# Yukari_3_11DoF_2_Unrouted.net
KiCad netlist of a schematic drawn in EAGLE
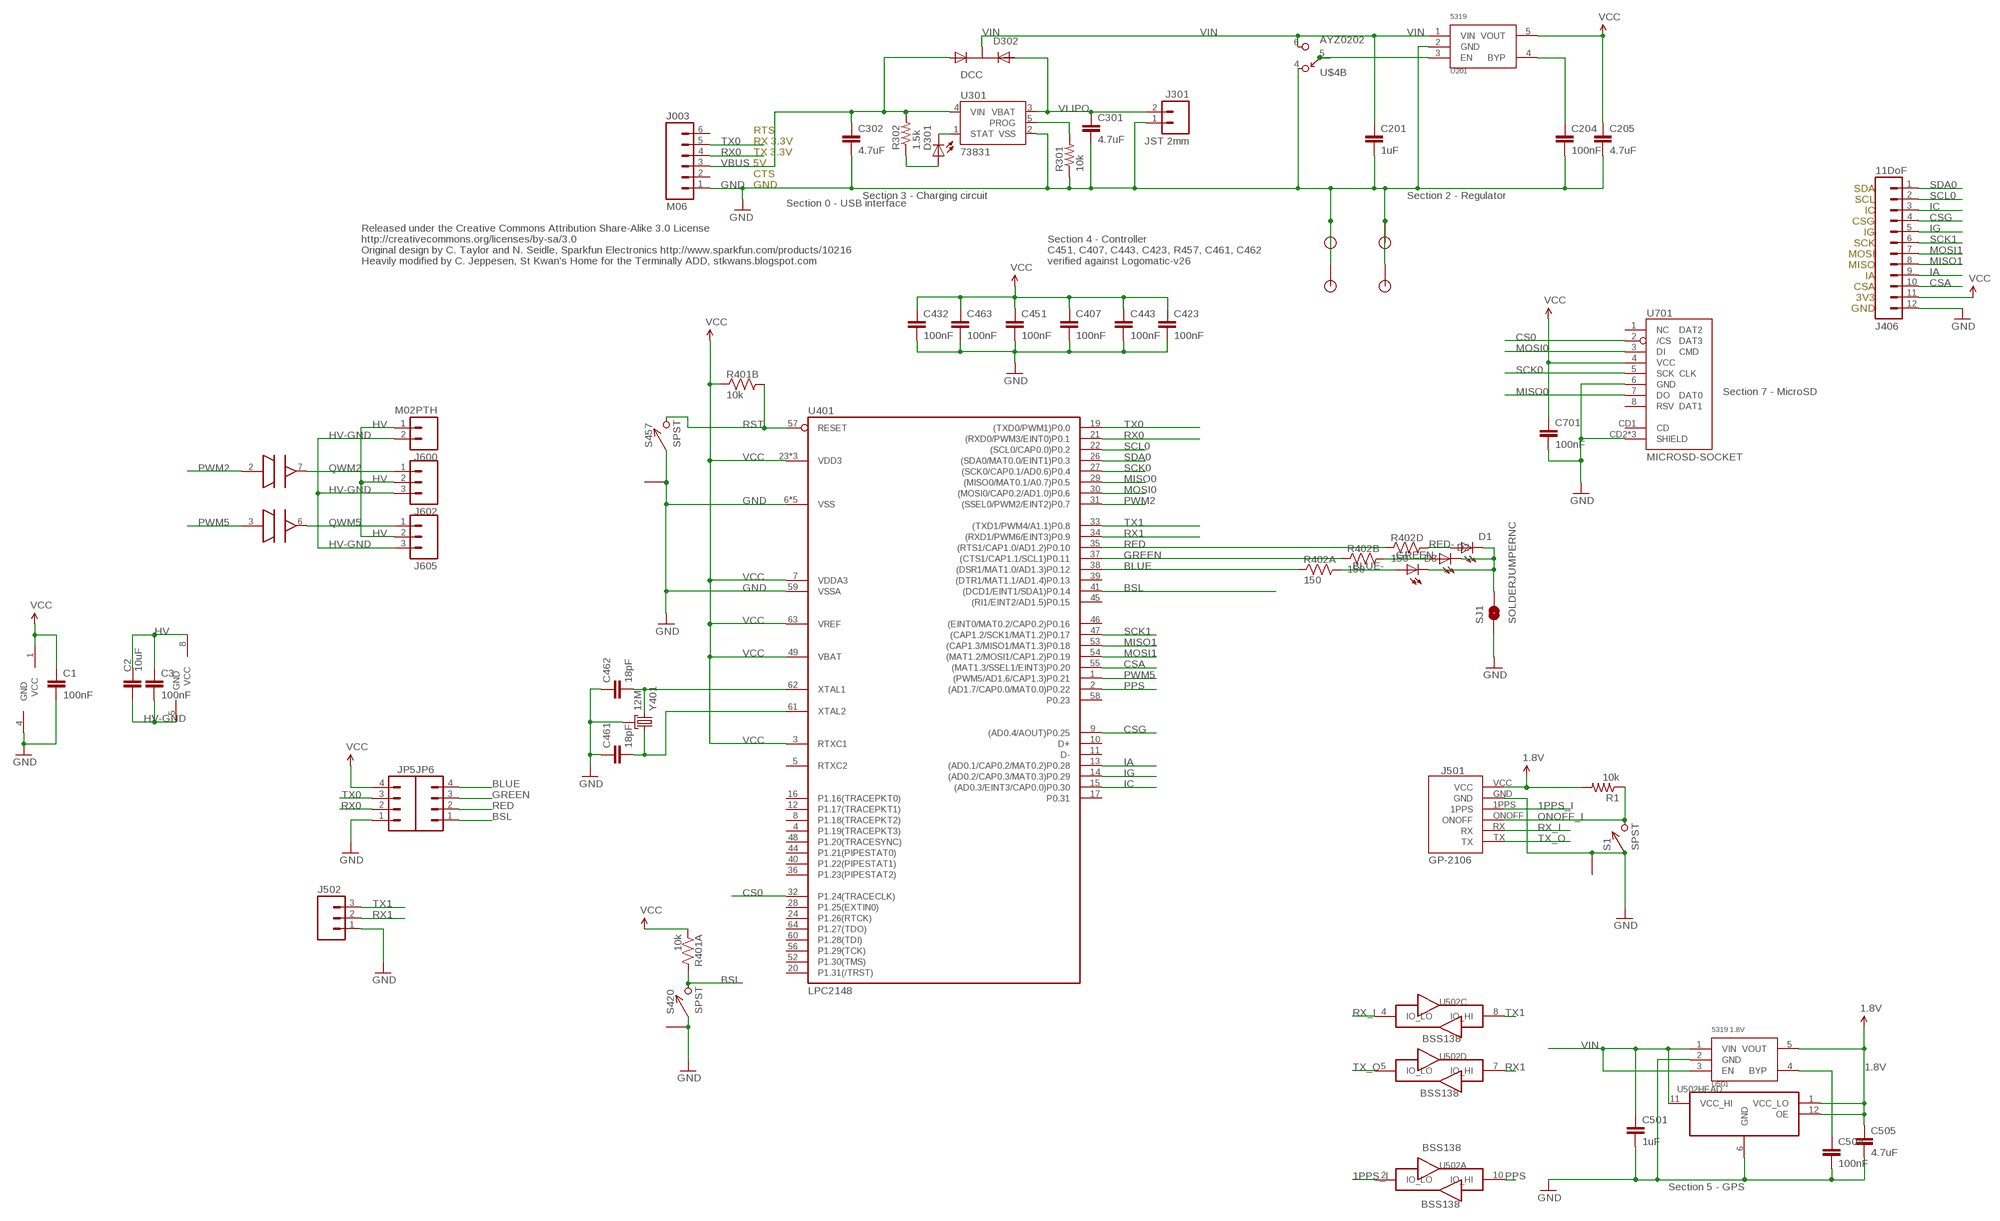
[diagram p0: schematic, sheet 1]

(export (version "E")
  (design (tool "Eeschema 10.0.6"))
  (components
    (comp (ref "C1")
      (value "100nF")
      (footprint "eagle-import:0402-CAP")
      (libsource (lib "eagle-import") (part "CAP0402-CAP"))
    )
    (comp (ref "C2")
      (value "10uF")
      (footprint "eagle-import:0603-CAP")
      (libsource (lib "eagle-import") (part "CAP0603-CAP"))
    )
    (comp (ref "C3")
      (value "100nF")
      (footprint "eagle-import:0402-CAP")
      (libsource (lib "eagle-import") (part "CAP0402-CAP"))
    )
    (comp (ref "C201")
      (value "1uF")
      (footprint "eagle-import:0402-CAP")
      (libsource (lib "eagle-import") (part "CAP0402-CAP"))
    )
    (comp (ref "C204")
      (value "100nF")
      (footprint "eagle-import:0402-CAP")
      (libsource (lib "eagle-import") (part "CAP0402-CAP"))
    )
    (comp (ref "C205")
      (value "4.7uF")
      (footprint "eagle-import:0402-CAP")
      (libsource (lib "eagle-import") (part "CAP0402-CAP"))
    )
    (comp (ref "C301")
      (value "4.7uF")
      (footprint "eagle-import:0402-CAP")
      (libsource (lib "eagle-import") (part "CAP0402-CAP"))
    )
    (comp (ref "C302")
      (value "4.7uF")
      (footprint "eagle-import:0402-CAP")
      (libsource (lib "eagle-import") (part "CAP0402-CAP"))
    )
    (comp (ref "C407")
      (value "100nF")
      (footprint "eagle-import:0402-CAP")
      (libsource (lib "eagle-import") (part "CAP0402-CAP"))
    )
    (comp (ref "C423")
      (value "100nF")
      (footprint "eagle-import:0402-CAP")
      (libsource (lib "eagle-import") (part "CAP0402-CAP"))
    )
    (comp (ref "C432")
      (value "100nF")
      (footprint "eagle-import:0402-CAP")
      (libsource (lib "eagle-import") (part "CAP0402-CAP"))
    )
    (comp (ref "C443")
      (value "100nF")
      (footprint "eagle-import:0402-CAP")
      (libsource (lib "eagle-import") (part "CAP0402-CAP"))
    )
    (comp (ref "C451")
      (value "100nF")
      (footprint "eagle-import:0402-CAP")
      (libsource (lib "eagle-import") (part "CAP0402-CAP"))
    )
    (comp (ref "C461")
      (value "18pF")
      (footprint "eagle-import:0402-CAP")
      (libsource (lib "eagle-import") (part "CAP0402-CAP"))
    )
    (comp (ref "C462")
      (value "18pF")
      (footprint "eagle-import:0402-CAP")
      (libsource (lib "eagle-import") (part "CAP0402-CAP"))
    )
    (comp (ref "C463")
      (value "100nF")
      (footprint "eagle-import:0402-CAP")
      (libsource (lib "eagle-import") (part "CAP0402-CAP"))
    )
    (comp (ref "C501")
      (value "1uF")
      (footprint "eagle-import:0402-CAP")
      (libsource (lib "eagle-import") (part "CAP0402-CAP"))
    )
    (comp (ref "C504")
      (value "100nF")
      (footprint "eagle-import:0402-CAP")
      (libsource (lib "eagle-import") (part "CAP0402-CAP"))
    )
    (comp (ref "C505")
      (value "4.7uF")
      (footprint "eagle-import:0402-CAP")
      (libsource (lib "eagle-import") (part "CAP0402-CAP"))
    )
    (comp (ref "C701")
      (value "100nF")
      (footprint "eagle-import:0402-CAP")
      (libsource (lib "eagle-import") (part "CAP0402-CAP"))
    )
    (comp (ref "D1")
      (value "RED")
      (footprint "eagle-import:LED-0603")
      (libsource (lib "eagle-import") (part "LED0603"))
    )
    (comp (ref "D2")
      (value "GREEN")
      (footprint "eagle-import:LED-0603")
      (libsource (lib "eagle-import") (part "LED0603"))
    )
    (comp (ref "D3")
      (value "BLUE")
      (footprint "eagle-import:LED-0603")
      (libsource (lib "eagle-import") (part "LED0603"))
    )
    (comp (ref "D301")
      (value "RED")
      (footprint "eagle-import:LED-0603")
      (libsource (lib "eagle-import") (part "LED0603"))
    )
    (comp (ref "D302")
      (value "DCC")
      (footprint "eagle-import:SOT-23-3")
      (libsource (lib "eagle-import") (part "PMEG2005CT"))
    )
    (comp (ref "J003")
      (value "M06")
      (footprint "eagle-import:1X06")
      (libsource (lib "eagle-import") (part "M06SIP"))
    )
    (comp (ref "J301")
      (value "JST 2mm")
      (footprint "eagle-import:JST-2-SMD")
      (libsource (lib "eagle-import") (part "M02-JST-2MM-SMT"))
    )
    (comp (ref "J406")
      (value "11DoF")
      (footprint "eagle-import:1X12")
      (libsource (lib "eagle-import") (part "M12PTH"))
    )
    (comp (ref "J501")
      (value "GP-2106")
      (footprint "eagle-import:GP-2106")
      (libsource (lib "eagle-import") (part "GP-2106"))
    )
    (comp (ref "J502")
      (value "M03PTH")
      (footprint "eagle-import:1X03")
      (libsource (lib "eagle-import") (part "M03PTH"))
    )
    (comp (ref "J600")
      (value "M02PTH")
      (footprint "eagle-import:1X02")
      (libsource (lib "eagle-import") (part "SparkFun-Connectors_M02PTH"))
    )
    (comp (ref "J602")
      (value "M03PTH")
      (footprint "eagle-import:1X03")
      (libsource (lib "eagle-import") (part "M03PTH"))
    )
    (comp (ref "J605")
      (value "M03PTH")
      (footprint "eagle-import:1X03")
      (libsource (lib "eagle-import") (part "M03PTH"))
    )
    (comp (ref "JP1")
      (value "STANDOFF")
      (footprint "eagle-import:STANDOFF")
      (libsource (lib "eagle-import") (part "STANDOFF"))
    )
    (comp (ref "JP2")
      (value "STANDOFF")
      (footprint "eagle-import:STANDOFF")
      (libsource (lib "eagle-import") (part "STANDOFF"))
    )
    (comp (ref "JP3")
      (value "STANDOFF")
      (footprint "eagle-import:STANDOFF")
      (libsource (lib "eagle-import") (part "STANDOFF"))
    )
    (comp (ref "JP4")
      (value "STANDOFF")
      (footprint "eagle-import:STANDOFF")
      (libsource (lib "eagle-import") (part "STANDOFF"))
    )
    (comp (ref "JP5")
      (value "M04PTH")
      (footprint "eagle-import:1X04")
      (libsource (lib "eagle-import") (part "M04PTH"))
    )
    (comp (ref "JP6")
      (value "M04PTH")
      (footprint "eagle-import:1X04")
      (libsource (lib "eagle-import") (part "M04PTH"))
    )
    (comp (ref "R1")
      (value "10k")
      (footprint "eagle-import:0402-RES")
      (libsource (lib "eagle-import") (part "RESISTOR0402-RES"))
    )
    (comp (ref "R301")
      (value "10k")
      (footprint "eagle-import:0402-RES")
      (libsource (lib "eagle-import") (part "RESISTOR0402-RES"))
    )
    (comp (ref "R302")
      (value "1.5k")
      (footprint "eagle-import:0402-RES")
      (libsource (lib "eagle-import") (part "RESISTOR0402-RES"))
    )
    (comp (ref "R401")
      (value "10k")
      (footprint "eagle-import:CRA02")
      (libsource (lib "eagle-import") (part "RP2EXB24V"))
    )
    (comp (ref "R402")
      (value "150")
      (footprint "eagle-import:CRA04")
      (libsource (lib "eagle-import") (part "RP404"))
    )
    (comp (ref "S1")
      (value "SPST")
      (footprint "eagle-import:B3U-1100P")
      (libsource (lib "eagle-import") (part "B3U-1100P"))
    )
    (comp (ref "S420")
      (value "SPST")
      (footprint "eagle-import:B3U-1100P")
      (libsource (lib "eagle-import") (part "B3U-1100P"))
    )
    (comp (ref "S457")
      (value "SPST")
      (footprint "eagle-import:B3U-1100P")
      (libsource (lib "eagle-import") (part "B3U-1100P"))
    )
    (comp (ref "SJ1")
      (value "SOLDERJUMPERNC")
      (footprint "eagle-import:SJ_2S")
      (libsource (lib "eagle-import") (part "SOLDERJUMPERNC"))
    )
    (comp (ref "U$4")
      (value "AYZ0202")
      (footprint "eagle-import:AYZ0202")
      (libsource (lib "eagle-import") (part "AYZ0202"))
    )
    (comp (ref "U201")
      (value "5319")
      (footprint "eagle-import:SOT-23-5")
      (libsource (lib "eagle-import") (part "MIC5319D5"))
    )
    (comp (ref "U301")
      (value "73831")
      (footprint "eagle-import:SOT23-5")
      (libsource (lib "eagle-import") (part "MCP73831"))
    )
    (comp (ref "U401")
      (value "LPC2148")
      (footprint "eagle-import:LQFP64")
      (libsource (lib "eagle-import") (part "LPC2148"))
    )
    (comp (ref "U501")
      (value "5319 1.8V")
      (footprint "eagle-import:SOT-23-5")
      (libsource (lib "eagle-import") (part "MIC5319D5"))
    )
    (comp (ref "U502")
      (value "TXB0104RUT")
      (footprint "eagle-import:R-PUQFN-N12")
      (libsource (lib "eagle-import") (part "TXB0104RUT"))
    )
    (comp (ref "U600")
      (value "ADUM3221")
      (footprint "eagle-import:SO8N")
      (libsource (lib "eagle-import") (part "ADUM3221"))
    )
    (comp (ref "U701")
      (value "MICROSD-SOCKET")
      (footprint "eagle-import:MICROSD-SOCKET-PP")
      (libsource (lib "eagle-import") (part "MICROSD-SOCKET"))
    )
    (comp (ref "Y401")
      (value "12M")
      (footprint "eagle-import:CRYSTAL_SMD")
      (libsource (lib "eagle-import") (part "TSX-3225"))
    )
  )
  (nets
    (net (code "1") (name "/1PPS_I") (class "Default")
      (node (ref "J501") (pin "1PPS") (pinfunction "1PPS_1PPS") (pintype "bidirectional"))
      (node (ref "U502") (pin "2") (pinfunction "IO_LO_2") (pintype "bidirectional"))
    )
    (net (code "2") (name "/BLUE") (class "Default")
      (node (ref "JP6") (pin "4") (pinfunction "4_4") (pintype "passive"))
      (node (ref "R402") (pin "1") (pinfunction "1_1") (pintype "passive"))
      (node (ref "U401") (pin "38") (pinfunction "(DSR1/MAT1.0/AD1.3)P0.12_38") (pintype "bidirectional"))
    )
    (net (code "3") (name "/BLUE-") (class "Default")
      (node (ref "D3") (pin "A") (pinfunction "A_A") (pintype "passive"))
      (node (ref "R402") (pin "8") (pinfunction "2_8") (pintype "passive"))
    )
    (net (code "4") (name "/BSL") (class "Default")
      (node (ref "JP6") (pin "1") (pinfunction "1_1") (pintype "passive"))
      (node (ref "R401") (pin "4") (pinfunction "2_4") (pintype "passive"))
      (node (ref "S420") (pin "P$2") (pinfunction "2_P$2") (pintype "bidirectional"))
      (node (ref "U401") (pin "41") (pinfunction "(DCD1/EINT1/SDA1)P0.14_41") (pintype "bidirectional"))
    )
    (net (code "5") (name "/CS0") (class "Default")
      (node (ref "U401") (pin "32") (pinfunction "P1.24(TRACECLK)_32") (pintype "bidirectional"))
      (node (ref "U701") (pin "2") (pinfunction "/CS_2") (pintype "bidirectional"))
    )
    (net (code "6") (name "/CSA") (class "Default")
      (node (ref "J406") (pin "10") (pinfunction "10_10") (pintype "passive"))
      (node (ref "U401") (pin "55") (pinfunction "(MAT1.3/SSEL1/EINT3)P0.20_55") (pintype "bidirectional"))
    )
    (net (code "7") (name "/CSG") (class "Default")
      (node (ref "J406") (pin "4") (pinfunction "4_4") (pintype "passive"))
      (node (ref "U401") (pin "9") (pinfunction "(AD0.4/AOUT)P0.25_9") (pintype "bidirectional"))
    )
    (net (code "8") (name "/GREEN") (class "Default")
      (node (ref "JP6") (pin "3") (pinfunction "3_3") (pintype "passive"))
      (node (ref "R402") (pin "2") (pinfunction "1_2") (pintype "passive"))
      (node (ref "U401") (pin "37") (pinfunction "(CTS1/CAP1.1/SCL1)P0.11_37") (pintype "bidirectional"))
    )
    (net (code "9") (name "/GREEN-") (class "Default")
      (node (ref "D2") (pin "A") (pinfunction "A_A") (pintype "passive"))
      (node (ref "R402") (pin "7") (pinfunction "2_7") (pintype "passive"))
    )
    (net (code "10") (name "/HV") (class "Default")
      (node (ref "C2") (pin "1") (pinfunction "1_1") (pintype "passive"))
      (node (ref "C3") (pin "1") (pinfunction "1_1") (pintype "passive"))
      (node (ref "J600") (pin "1") (pinfunction "1_1") (pintype "passive"))
      (node (ref "J602") (pin "2") (pinfunction "2_2") (pintype "passive"))
      (node (ref "J605") (pin "2") (pinfunction "2_2") (pintype "passive"))
      (node (ref "U600") (pin "8") (pinfunction "VCC_8") (pintype "bidirectional"))
    )
    (net (code "11") (name "/HV-GND") (class "Default")
      (node (ref "C2") (pin "2") (pinfunction "2_2") (pintype "passive"))
      (node (ref "C3") (pin "2") (pinfunction "2_2") (pintype "passive"))
      (node (ref "J600") (pin "2") (pinfunction "2_2") (pintype "passive"))
      (node (ref "J602") (pin "3") (pinfunction "3_3") (pintype "passive"))
      (node (ref "J605") (pin "3") (pinfunction "3_3") (pintype "passive"))
      (node (ref "U600") (pin "5") (pinfunction "GND_5") (pintype "bidirectional"))
    )
    (net (code "12") (name "/IA") (class "Default")
      (node (ref "J406") (pin "9") (pinfunction "9_9") (pintype "passive"))
      (node (ref "U401") (pin "13") (pinfunction "(AD0.1/CAP0.2/MAT0.2)P0.28_13") (pintype "bidirectional"))
    )
    (net (code "13") (name "/IC") (class "Default")
      (node (ref "J406") (pin "3") (pinfunction "3_3") (pintype "passive"))
      (node (ref "U401") (pin "15") (pinfunction "(AD0.3/EINT3/CAP0.0)P0.30_15") (pintype "bidirectional"))
    )
    (net (code "14") (name "/IG") (class "Default")
      (node (ref "J406") (pin "5") (pinfunction "5_5") (pintype "passive"))
      (node (ref "U401") (pin "14") (pinfunction "(AD0.2/CAP0.3/MAT0.3)P0.29_14") (pintype "bidirectional"))
    )
    (net (code "15") (name "/MISO0") (class "Default")
      (node (ref "U401") (pin "29") (pinfunction "(MISO0/MAT0.1/A0.7)P0.5_29") (pintype "bidirectional"))
      (node (ref "U701") (pin "7") (pinfunction "DO_7") (pintype "bidirectional"))
    )
    (net (code "16") (name "/MISO1") (class "Default")
      (node (ref "J406") (pin "8") (pinfunction "8_8") (pintype "passive"))
      (node (ref "U401") (pin "53") (pinfunction "(CAP1.3/MISO1/MAT1.3)P0.18_53") (pintype "bidirectional"))
    )
    (net (code "17") (name "/MOSI0") (class "Default")
      (node (ref "U401") (pin "30") (pinfunction "(MOSI0/CAP0.2/AD1.0)P0.6_30") (pintype "bidirectional"))
      (node (ref "U701") (pin "3") (pinfunction "DI_3") (pintype "bidirectional"))
    )
    (net (code "18") (name "/MOSI1") (class "Default")
      (node (ref "J406") (pin "7") (pinfunction "7_7") (pintype "passive"))
      (node (ref "U401") (pin "54") (pinfunction "(MAT1.2/MOSI1/CAP1.2)P0.19_54") (pintype "bidirectional"))
    )
    (net (code "19") (name "/ONOFF_I") (class "Default")
      (node (ref "J501") (pin "ONOFF") (pinfunction "ONOFF_ONOFF") (pintype "bidirectional"))
      (node (ref "R1") (pin "1") (pinfunction "1_1") (pintype "passive"))
      (node (ref "S1") (pin "P$2") (pinfunction "2_P$2") (pintype "bidirectional"))
    )
    (net (code "20") (name "/PPS") (class "Default")
      (node (ref "U401") (pin "2") (pinfunction "(AD1.7/CAP0.0/MAT0.0)P0.22_2") (pintype "bidirectional"))
      (node (ref "U502") (pin "10") (pinfunction "IO_HI_10") (pintype "bidirectional"))
    )
    (net (code "21") (name "/PWM2") (class "Default")
      (node (ref "U401") (pin "31") (pinfunction "(SSEL0/PWM2/EINT2)P0.7_31") (pintype "bidirectional"))
      (node (ref "U600") (pin "2") (pinfunction "IN_2") (pintype "input"))
    )
    (net (code "22") (name "/PWM5") (class "Default")
      (node (ref "U401") (pin "1") (pinfunction "(PWM5/AD1.6/CAP1.3)P0.21_1") (pintype "bidirectional"))
      (node (ref "U600") (pin "3") (pinfunction "IN_3") (pintype "input"))
    )
    (net (code "23") (name "/QWM2") (class "Default")
      (node (ref "J602") (pin "1") (pinfunction "1_1") (pintype "passive"))
      (node (ref "U600") (pin "7") (pinfunction "OUT_7") (pintype "bidirectional"))
    )
    (net (code "24") (name "/QWM5") (class "Default")
      (node (ref "J605") (pin "1") (pinfunction "1_1") (pintype "passive"))
      (node (ref "U600") (pin "6") (pinfunction "OUT_6") (pintype "bidirectional"))
    )
    (net (code "25") (name "/RED") (class "Default")
      (node (ref "JP6") (pin "2") (pinfunction "2_2") (pintype "passive"))
      (node (ref "R402") (pin "4") (pinfunction "1_4") (pintype "passive"))
      (node (ref "U401") (pin "35") (pinfunction "(RTS1/CAP1.0/AD1.2)P0.10_35") (pintype "bidirectional"))
    )
    (net (code "26") (name "/RED-") (class "Default")
      (node (ref "D1") (pin "A") (pinfunction "A_A") (pintype "passive"))
      (node (ref "R402") (pin "5") (pinfunction "2_5") (pintype "passive"))
    )
    (net (code "27") (name "/RST") (class "Default")
      (node (ref "R401") (pin "3") (pinfunction "2_3") (pintype "passive"))
      (node (ref "S457") (pin "P$2") (pinfunction "2_P$2") (pintype "bidirectional"))
      (node (ref "U401") (pin "57") (pinfunction "RESET_57") (pintype "input"))
    )
    (net (code "28") (name "/RX0") (class "Default")
      (node (ref "J003") (pin "4") (pinfunction "4_4") (pintype "passive"))
      (node (ref "JP5") (pin "2") (pinfunction "2_2") (pintype "passive"))
      (node (ref "U401") (pin "21") (pinfunction "(RXD0/PWM3/EINT0)P0.1_21") (pintype "bidirectional"))
    )
    (net (code "29") (name "/RX1") (class "Default")
      (node (ref "J502") (pin "2") (pinfunction "2_2") (pintype "passive"))
      (node (ref "U401") (pin "34") (pinfunction "(RXD1/PWM6/EINT3)P0.9_34") (pintype "bidirectional"))
      (node (ref "U502") (pin "7") (pinfunction "IO_HI_7") (pintype "bidirectional"))
    )
    (net (code "30") (name "/RX_I") (class "Default")
      (node (ref "J501") (pin "RX") (pinfunction "RX_RX") (pintype "bidirectional"))
      (node (ref "U502") (pin "4") (pinfunction "IO_LO_4") (pintype "bidirectional"))
    )
    (net (code "31") (name "/SCK0") (class "Default")
      (node (ref "U401") (pin "27") (pinfunction "(SCK0/CAP0.1/AD0.6)P0.4_27") (pintype "bidirectional"))
      (node (ref "U701") (pin "5") (pinfunction "SCK_5") (pintype "bidirectional"))
    )
    (net (code "32") (name "/SCK1") (class "Default")
      (node (ref "J406") (pin "6") (pinfunction "6_6") (pintype "passive"))
      (node (ref "U401") (pin "47") (pinfunction "(CAP1.2/SCK1/MAT1.2)P0.17_47") (pintype "bidirectional"))
    )
    (net (code "33") (name "/SCL0") (class "Default")
      (node (ref "J406") (pin "2") (pinfunction "2_2") (pintype "passive"))
      (node (ref "U401") (pin "22") (pinfunction "(SCL0/CAP0.0)P0.2_22") (pintype "bidirectional"))
    )
    (net (code "34") (name "/SDA0") (class "Default")
      (node (ref "J406") (pin "1") (pinfunction "1_1") (pintype "passive"))
      (node (ref "U401") (pin "26") (pinfunction "(SDA0/MAT0.0/EINT1)P0.3_26") (pintype "bidirectional"))
    )
    (net (code "35") (name "/TX0") (class "Default")
      (node (ref "J003") (pin "5") (pinfunction "5_5") (pintype "passive"))
      (node (ref "JP5") (pin "3") (pinfunction "3_3") (pintype "passive"))
      (node (ref "U401") (pin "19") (pinfunction "(TXD0/PWM1)P0.0_19") (pintype "bidirectional"))
    )
    (net (code "36") (name "/TX1") (class "Default")
      (node (ref "J502") (pin "3") (pinfunction "3_3") (pintype "passive"))
      (node (ref "U401") (pin "33") (pinfunction "(TXD1/PWM4/A1.1)P0.8_33") (pintype "bidirectional"))
      (node (ref "U502") (pin "8") (pinfunction "IO_HI_8") (pintype "bidirectional"))
    )
    (net (code "37") (name "/TX_O") (class "Default")
      (node (ref "J501") (pin "TX") (pinfunction "TX_TX") (pintype "bidirectional"))
      (node (ref "U502") (pin "5") (pinfunction "IO_LO_5") (pintype "bidirectional"))
    )
    (net (code "38") (name "/VBUS") (class "Default")
      (node (ref "C302") (pin "1") (pinfunction "1_1") (pintype "passive"))
      (node (ref "D302") (pin "1") (pinfunction "A1_1") (pintype "passive"))
      (node (ref "J003") (pin "3") (pinfunction "3_3") (pintype "passive"))
      (node (ref "R302") (pin "2") (pinfunction "2_2") (pintype "passive"))
      (node (ref "U301") (pin "4") (pinfunction "VIN_4") (pintype "power_in"))
    )
    (net (code "39") (name "/VIN") (class "Default")
      (node (ref "C201") (pin "1") (pinfunction "1_1") (pintype "passive"))
      (node (ref "C501") (pin "1") (pinfunction "1_1") (pintype "passive"))
      (node (ref "D302") (pin "3") (pinfunction "K_3") (pintype "passive"))
      (node (ref "U$4") (pin "6") (pinfunction "P$2_6") (pintype "bidirectional"))
      (node (ref "U201") (pin "1") (pinfunction "VIN_1") (pintype "bidirectional"))
      (node (ref "U501") (pin "1") (pinfunction "VIN_1") (pintype "bidirectional"))
      (node (ref "U501") (pin "3") (pinfunction "EN_3") (pintype "bidirectional"))
      (node (ref "U502") (pin "11") (pinfunction "VCC_HI_11") (pintype "power_in"))
    )
    (net (code "40") (name "/VLIPO") (class "Default")
      (node (ref "C301") (pin "1") (pinfunction "1_1") (pintype "passive"))
      (node (ref "D302") (pin "2") (pinfunction "A2_2") (pintype "passive"))
      (node (ref "J301") (pin "2") (pinfunction "2_2") (pintype "passive"))
      (node (ref "U301") (pin "3") (pinfunction "VBAT_3") (pintype "power_in"))
    )
    (net (code "41") (name "1.8V") (class "Default")
      (node (ref "C505") (pin "1") (pinfunction "1_1") (pintype "passive"))
      (node (ref "J501") (pin "VCC") (pinfunction "VCC_VCC") (pintype "bidirectional"))
      (node (ref "R1") (pin "2") (pinfunction "2_2") (pintype "passive"))
      (node (ref "U501") (pin "5") (pinfunction "VOUT_5") (pintype "bidirectional"))
      (node (ref "U502") (pin "1") (pinfunction "VCC_LO_1") (pintype "power_in"))
      (node (ref "U502") (pin "12") (pinfunction "OE_12") (pintype "bidirectional"))
    )
    (net (code "42") (name "GND") (class "Default")
      (node (ref "C1") (pin "2") (pinfunction "2_2") (pintype "passive"))
      (node (ref "C201") (pin "2") (pinfunction "2_2") (pintype "passive"))
      (node (ref "C204") (pin "2") (pinfunction "2_2") (pintype "passive"))
      (node (ref "C205") (pin "2") (pinfunction "2_2") (pintype "passive"))
      (node (ref "C301") (pin "2") (pinfunction "2_2") (pintype "passive"))
      (node (ref "C302") (pin "2") (pinfunction "2_2") (pintype "passive"))
      (node (ref "C407") (pin "2") (pinfunction "2_2") (pintype "passive"))
      (node (ref "C423") (pin "2") (pinfunction "2_2") (pintype "passive"))
      (node (ref "C432") (pin "2") (pinfunction "2_2") (pintype "passive"))
      (node (ref "C443") (pin "2") (pinfunction "2_2") (pintype "passive"))
      (node (ref "C451") (pin "2") (pinfunction "2_2") (pintype "passive"))
      (node (ref "C461") (pin "1") (pinfunction "1_1") (pintype "passive"))
      (node (ref "C462") (pin "1") (pinfunction "1_1") (pintype "passive"))
      (node (ref "C463") (pin "2") (pinfunction "2_2") (pintype "passive"))
      (node (ref "C501") (pin "2") (pinfunction "2_2") (pintype "passive"))
      (node (ref "C504") (pin "2") (pinfunction "2_2") (pintype "passive"))
      (node (ref "C505") (pin "2") (pinfunction "2_2") (pintype "passive"))
      (node (ref "C701") (pin "2") (pinfunction "2_2") (pintype "passive"))
      (node (ref "J003") (pin "1") (pinfunction "1_1") (pintype "passive"))
      (node (ref "J301") (pin "1") (pinfunction "1_1") (pintype "passive"))
      (node (ref "J406") (pin "12") (pinfunction "12_12") (pintype "passive"))
      (node (ref "J501") (pin "GND") (pinfunction "GND_GND") (pintype "bidirectional"))
      (node (ref "J502") (pin "1") (pinfunction "1_1") (pintype "passive"))
      (node (ref "JP1") (pin "P$1") (pinfunction "P$1_P$1") (pintype "bidirectional"))
      (node (ref "JP2") (pin "P$1") (pinfunction "P$1_P$1") (pintype "bidirectional"))
      (node (ref "JP3") (pin "P$1") (pinfunction "P$1_P$1") (pintype "bidirectional"))
      (node (ref "JP4") (pin "P$1") (pinfunction "P$1_P$1") (pintype "bidirectional"))
      (node (ref "JP5") (pin "1") (pinfunction "1_1") (pintype "passive"))
      (node (ref "R301") (pin "1") (pinfunction "1_1") (pintype "passive"))
      (node (ref "S1") (pin "P$1") (pinfunction "1_P$1") (pintype "bidirectional"))
      (node (ref "S1") (pin "P$3") (pinfunction "1_P$3") (pintype "bidirectional"))
      (node (ref "S420") (pin "P$1") (pinfunction "1_P$1") (pintype "bidirectional"))
      (node (ref "S420") (pin "P$3") (pinfunction "1_P$3") (pintype "bidirectional"))
      (node (ref "S457") (pin "P$1") (pinfunction "1_P$1") (pintype "bidirectional"))
      (node (ref "S457") (pin "P$3") (pinfunction "1_P$3") (pintype "bidirectional"))
      (node (ref "SJ1") (pin "1") (pinfunction "1_1") (pintype "passive"))
      (node (ref "U$4") (pin "4") (pinfunction "P$1_4") (pintype "bidirectional"))
      (node (ref "U201") (pin "2") (pinfunction "GND_2") (pintype "bidirectional"))
      (node (ref "U301") (pin "2") (pinfunction "VSS_2") (pintype "power_in"))
      (node (ref "U401") (pin "18") (pinfunction "VSS_18") (pintype "power_in"))
      (node (ref "U401") (pin "25") (pinfunction "VSS_25") (pintype "power_in"))
      (node (ref "U401") (pin "42") (pinfunction "VSS_42") (pintype "power_in"))
      (node (ref "U401") (pin "50") (pinfunction "VSS_50") (pintype "power_in"))
      (node (ref "U401") (pin "59") (pinfunction "VSSA_59") (pintype "power_in"))
      (node (ref "U401") (pin "6") (pinfunction "VSS_6") (pintype "power_in"))
      (node (ref "U501") (pin "2") (pinfunction "GND_2") (pintype "bidirectional"))
      (node (ref "U502") (pin "6") (pinfunction "GND_6") (pintype "power_in"))
      (node (ref "U600") (pin "4") (pinfunction "GND_4") (pintype "bidirectional"))
      (node (ref "U701") (pin "6") (pinfunction "GND_6") (pintype "bidirectional"))
      (node (ref "U701") (pin "CD2") (pinfunction "SHIELD_CD2") (pintype "bidirectional"))
      (node (ref "U701") (pin "GND1") (pinfunction "SHIELD_GND1") (pintype "bidirectional"))
      (node (ref "U701") (pin "GND3") (pinfunction "SHIELD_GND3") (pintype "bidirectional"))
      (node (ref "Y401") (pin "2") (pinfunction "GND_2") (pintype "passive"))
      (node (ref "Y401") (pin "4") (pinfunction "GND_4") (pintype "passive"))
    )
    (net (code "43") (name "Net-(D1-PadC)") (class "Default")
      (node (ref "D1") (pin "C") (pinfunction "C_C") (pintype "passive"))
      (node (ref "D2") (pin "C") (pinfunction "C_C") (pintype "passive"))
      (node (ref "D3") (pin "C") (pinfunction "C_C") (pintype "passive"))
      (node (ref "SJ1") (pin "2") (pinfunction "2_2") (pintype "passive"))
    )
    (net (code "44") (name "Net-(D301-PadA)") (class "Default")
      (node (ref "D301") (pin "A") (pinfunction "A_A") (pintype "passive"))
      (node (ref "R302") (pin "1") (pinfunction "1_1") (pintype "passive"))
    )
    (net (code "45") (name "Net-(U$4B-P$3)") (class "Default")
      (node (ref "U$4") (pin "5") (pinfunction "P$3_5") (pintype "bidirectional"))
      (node (ref "U201") (pin "3") (pinfunction "EN_3") (pintype "bidirectional"))
    )
    (net (code "46") (name "Net-(U201-BYP)") (class "Default")
      (node (ref "C204") (pin "1") (pinfunction "1_1") (pintype "passive"))
      (node (ref "U201") (pin "4") (pinfunction "BYP_4") (pintype "bidirectional"))
    )
    (net (code "47") (name "Net-(U301-PROG)") (class "Default")
      (node (ref "R301") (pin "2") (pinfunction "2_2") (pintype "passive"))
      (node (ref "U301") (pin "5") (pinfunction "PROG_5") (pintype "input"))
    )
    (net (code "48") (name "Net-(U301-STAT)") (class "Default")
      (node (ref "D301") (pin "C") (pinfunction "C_C") (pintype "passive"))
      (node (ref "U301") (pin "1") (pinfunction "STAT_1") (pintype "output"))
    )
    (net (code "49") (name "Net-(U401-XTAL1)") (class "Default")
      (node (ref "C462") (pin "2") (pinfunction "2_2") (pintype "passive"))
      (node (ref "U401") (pin "62") (pinfunction "XTAL1_62") (pintype "input"))
      (node (ref "Y401") (pin "3") (pinfunction "2_3") (pintype "passive"))
    )
    (net (code "50") (name "Net-(U401-XTAL2)") (class "Default")
      (node (ref "C461") (pin "2") (pinfunction "2_2") (pintype "passive"))
      (node (ref "U401") (pin "61") (pinfunction "XTAL2_61") (pintype "output"))
      (node (ref "Y401") (pin "1") (pinfunction "1_1") (pintype "passive"))
    )
    (net (code "51") (name "Net-(U501-BYP)") (class "Default")
      (node (ref "C504") (pin "1") (pinfunction "1_1") (pintype "passive"))
      (node (ref "U501") (pin "4") (pinfunction "BYP_4") (pintype "bidirectional"))
    )
    (net (code "52") (name "VCC") (class "Default")
      (node (ref "C1") (pin "1") (pinfunction "1_1") (pintype "passive"))
      (node (ref "C205") (pin "1") (pinfunction "1_1") (pintype "passive"))
      (node (ref "C407") (pin "1") (pinfunction "1_1") (pintype "passive"))
      (node (ref "C423") (pin "1") (pinfunction "1_1") (pintype "passive"))
      (node (ref "C432") (pin "1") (pinfunction "1_1") (pintype "passive"))
      (node (ref "C443") (pin "1") (pinfunction "1_1") (pintype "passive"))
      (node (ref "C451") (pin "1") (pinfunction "1_1") (pintype "passive"))
      (node (ref "C463") (pin "1") (pinfunction "1_1") (pintype "passive"))
      (node (ref "C701") (pin "1") (pinfunction "1_1") (pintype "passive"))
      (node (ref "J406") (pin "11") (pinfunction "11_11") (pintype "passive"))
      (node (ref "JP5") (pin "4") (pinfunction "4_4") (pintype "passive"))
      (node (ref "R401") (pin "1") (pinfunction "1_1") (pintype "passive"))
      (node (ref "R401") (pin "2") (pinfunction "1_2") (pintype "passive"))
      (node (ref "U201") (pin "5") (pinfunction "VOUT_5") (pintype "bidirectional"))
      (node (ref "U401") (pin "23") (pinfunction "VDD3_23") (pintype "power_in"))
      (node (ref "U401") (pin "3") (pinfunction "RTXC1_3") (pintype "input"))
      (node (ref "U401") (pin "43") (pinfunction "VDD3_43") (pintype "power_in"))
      (node (ref "U401") (pin "49") (pinfunction "VBAT_49") (pintype "power_in"))
      (node (ref "U401") (pin "51") (pinfunction "VDD3_51") (pintype "power_in"))
      (node (ref "U401") (pin "63") (pinfunction "VREF_63") (pintype "input"))
      (node (ref "U401") (pin "7") (pinfunction "VDDA3_7") (pintype "power_in"))
      (node (ref "U600") (pin "1") (pinfunction "VCC_1") (pintype "bidirectional"))
      (node (ref "U701") (pin "4") (pinfunction "VCC_4") (pintype "bidirectional"))
    )
    (net (code "53") (name "unconnected-(J003-Pad2)") (class "Default")
      (node (ref "J003") (pin "2") (pinfunction "2_2") (pintype "passive"))
    )
    (net (code "54") (name "unconnected-(J003-Pad6)") (class "Default")
      (node (ref "J003") (pin "6") (pinfunction "6_6") (pintype "passive"))
    )
    (net (code "55") (name "unconnected-(U401-(DTR1{slash}MAT1.1{slash}AD1.4)P0.13-Pad39)") (class "Default")
      (node (ref "U401") (pin "39") (pinfunction "(DTR1/MAT1.1/AD1.4)P0.13_39") (pintype "bidirectional"))
    )
    (net (code "56") (name "unconnected-(U401-(EINT0{slash}MAT0.2{slash}CAP0.2)P0.16-Pad46)") (class "Default")
      (node (ref "U401") (pin "46") (pinfunction "(EINT0/MAT0.2/CAP0.2)P0.16_46") (pintype "bidirectional"))
    )
    (net (code "57") (name "unconnected-(U401-(RI1{slash}EINT2{slash}AD1.5)P0.15-Pad45)") (class "Default")
      (node (ref "U401") (pin "45") (pinfunction "(RI1/EINT2/AD1.5)P0.15_45") (pintype "bidirectional"))
    )
    (net (code "58") (name "unconnected-(U401-D+-Pad10)") (class "Default")
      (node (ref "U401") (pin "10") (pinfunction "D+_10") (pintype "bidirectional"))
    )
    (net (code "59") (name "unconnected-(U401-D--Pad11)") (class "Default")
      (node (ref "U401") (pin "11") (pinfunction "D-_11") (pintype "bidirectional"))
    )
    (net (code "60") (name "unconnected-(U401-P0.23-Pad58)") (class "Default")
      (node (ref "U401") (pin "58") (pinfunction "P0.23_58") (pintype "bidirectional"))
    )
    (net (code "61") (name "unconnected-(U401-P0.31-Pad17)") (class "Default")
      (node (ref "U401") (pin "17") (pinfunction "P0.31_17") (pintype "output"))
    )
    (net (code "62") (name "unconnected-(U401-P1.16(TRACEPKT0)-Pad16)") (class "Default")
      (node (ref "U401") (pin "16") (pinfunction "P1.16(TRACEPKT0)_16") (pintype "bidirectional"))
    )
    (net (code "63") (name "unconnected-(U401-P1.17(TRACEPKT1)-Pad12)") (class "Default")
      (node (ref "U401") (pin "12") (pinfunction "P1.17(TRACEPKT1)_12") (pintype "bidirectional"))
    )
    (net (code "64") (name "unconnected-(U401-P1.18(TRACEPKT2)-Pad8)") (class "Default")
      (node (ref "U401") (pin "8") (pinfunction "P1.18(TRACEPKT2)_8") (pintype "bidirectional"))
    )
    (net (code "65") (name "unconnected-(U401-P1.19(TRACEPKT3)-Pad4)") (class "Default")
      (node (ref "U401") (pin "4") (pinfunction "P1.19(TRACEPKT3)_4") (pintype "bidirectional"))
    )
    (net (code "66") (name "unconnected-(U401-P1.20(TRACESYNC)-Pad48)") (class "Default")
      (node (ref "U401") (pin "48") (pinfunction "P1.20(TRACESYNC)_48") (pintype "bidirectional"))
    )
    (net (code "67") (name "unconnected-(U401-P1.21(PIPESTAT0)-Pad44)") (class "Default")
      (node (ref "U401") (pin "44") (pinfunction "P1.21(PIPESTAT0)_44") (pintype "bidirectional"))
    )
    (net (code "68") (name "unconnected-(U401-P1.22(PIPESTAT1)-Pad40)") (class "Default")
      (node (ref "U401") (pin "40") (pinfunction "P1.22(PIPESTAT1)_40") (pintype "bidirectional"))
    )
    (net (code "69") (name "unconnected-(U401-P1.23(PIPESTAT2)-Pad36)") (class "Default")
      (node (ref "U401") (pin "36") (pinfunction "P1.23(PIPESTAT2)_36") (pintype "bidirectional"))
    )
    (net (code "70") (name "unconnected-(U401-P1.25(EXTIN0)-Pad28)") (class "Default")
      (node (ref "U401") (pin "28") (pinfunction "P1.25(EXTIN0)_28") (pintype "bidirectional"))
    )
    (net (code "71") (name "unconnected-(U401-P1.26(RTCK)-Pad24)") (class "Default")
      (node (ref "U401") (pin "24") (pinfunction "P1.26(RTCK)_24") (pintype "bidirectional"))
    )
    (net (code "72") (name "unconnected-(U401-P1.27(TDO)-Pad64)") (class "Default")
      (node (ref "U401") (pin "64") (pinfunction "P1.27(TDO)_64") (pintype "bidirectional"))
    )
    (net (code "73") (name "unconnected-(U401-P1.28(TDI)-Pad60)") (class "Default")
      (node (ref "U401") (pin "60") (pinfunction "P1.28(TDI)_60") (pintype "bidirectional"))
    )
    (net (code "74") (name "unconnected-(U401-P1.29(TCK)-Pad56)") (class "Default")
      (node (ref "U401") (pin "56") (pinfunction "P1.29(TCK)_56") (pintype "bidirectional"))
    )
    (net (code "75") (name "unconnected-(U401-P1.30(TMS)-Pad52)") (class "Default")
      (node (ref "U401") (pin "52") (pinfunction "P1.30(TMS)_52") (pintype "bidirectional"))
    )
    (net (code "76") (name "unconnected-(U401-P1.31({slash}TRST)-Pad20)") (class "Default")
      (node (ref "U401") (pin "20") (pinfunction "P1.31(/TRST)_20") (pintype "bidirectional"))
    )
    (net (code "77") (name "unconnected-(U401-RTXC2-Pad5)") (class "Default")
      (node (ref "U401") (pin "5") (pinfunction "RTXC2_5") (pintype "output"))
    )
    (net (code "78") (name "unconnected-(U701-CD-PadCD1)") (class "Default")
      (node (ref "U701") (pin "CD1") (pinfunction "CD_CD1") (pintype "bidirectional"))
    )
    (net (code "79") (name "unconnected-(U701-NC-Pad1)") (class "Default")
      (node (ref "U701") (pin "1") (pinfunction "NC_1") (pintype "bidirectional"))
    )
    (net (code "80") (name "unconnected-(U701-RSV-Pad8)") (class "Default")
      (node (ref "U701") (pin "8") (pinfunction "RSV_8") (pintype "bidirectional"))
    )
  )
)
